# 16-FPGA-02a.net
KiCad netlist of a schematic drawn in Altium Designer
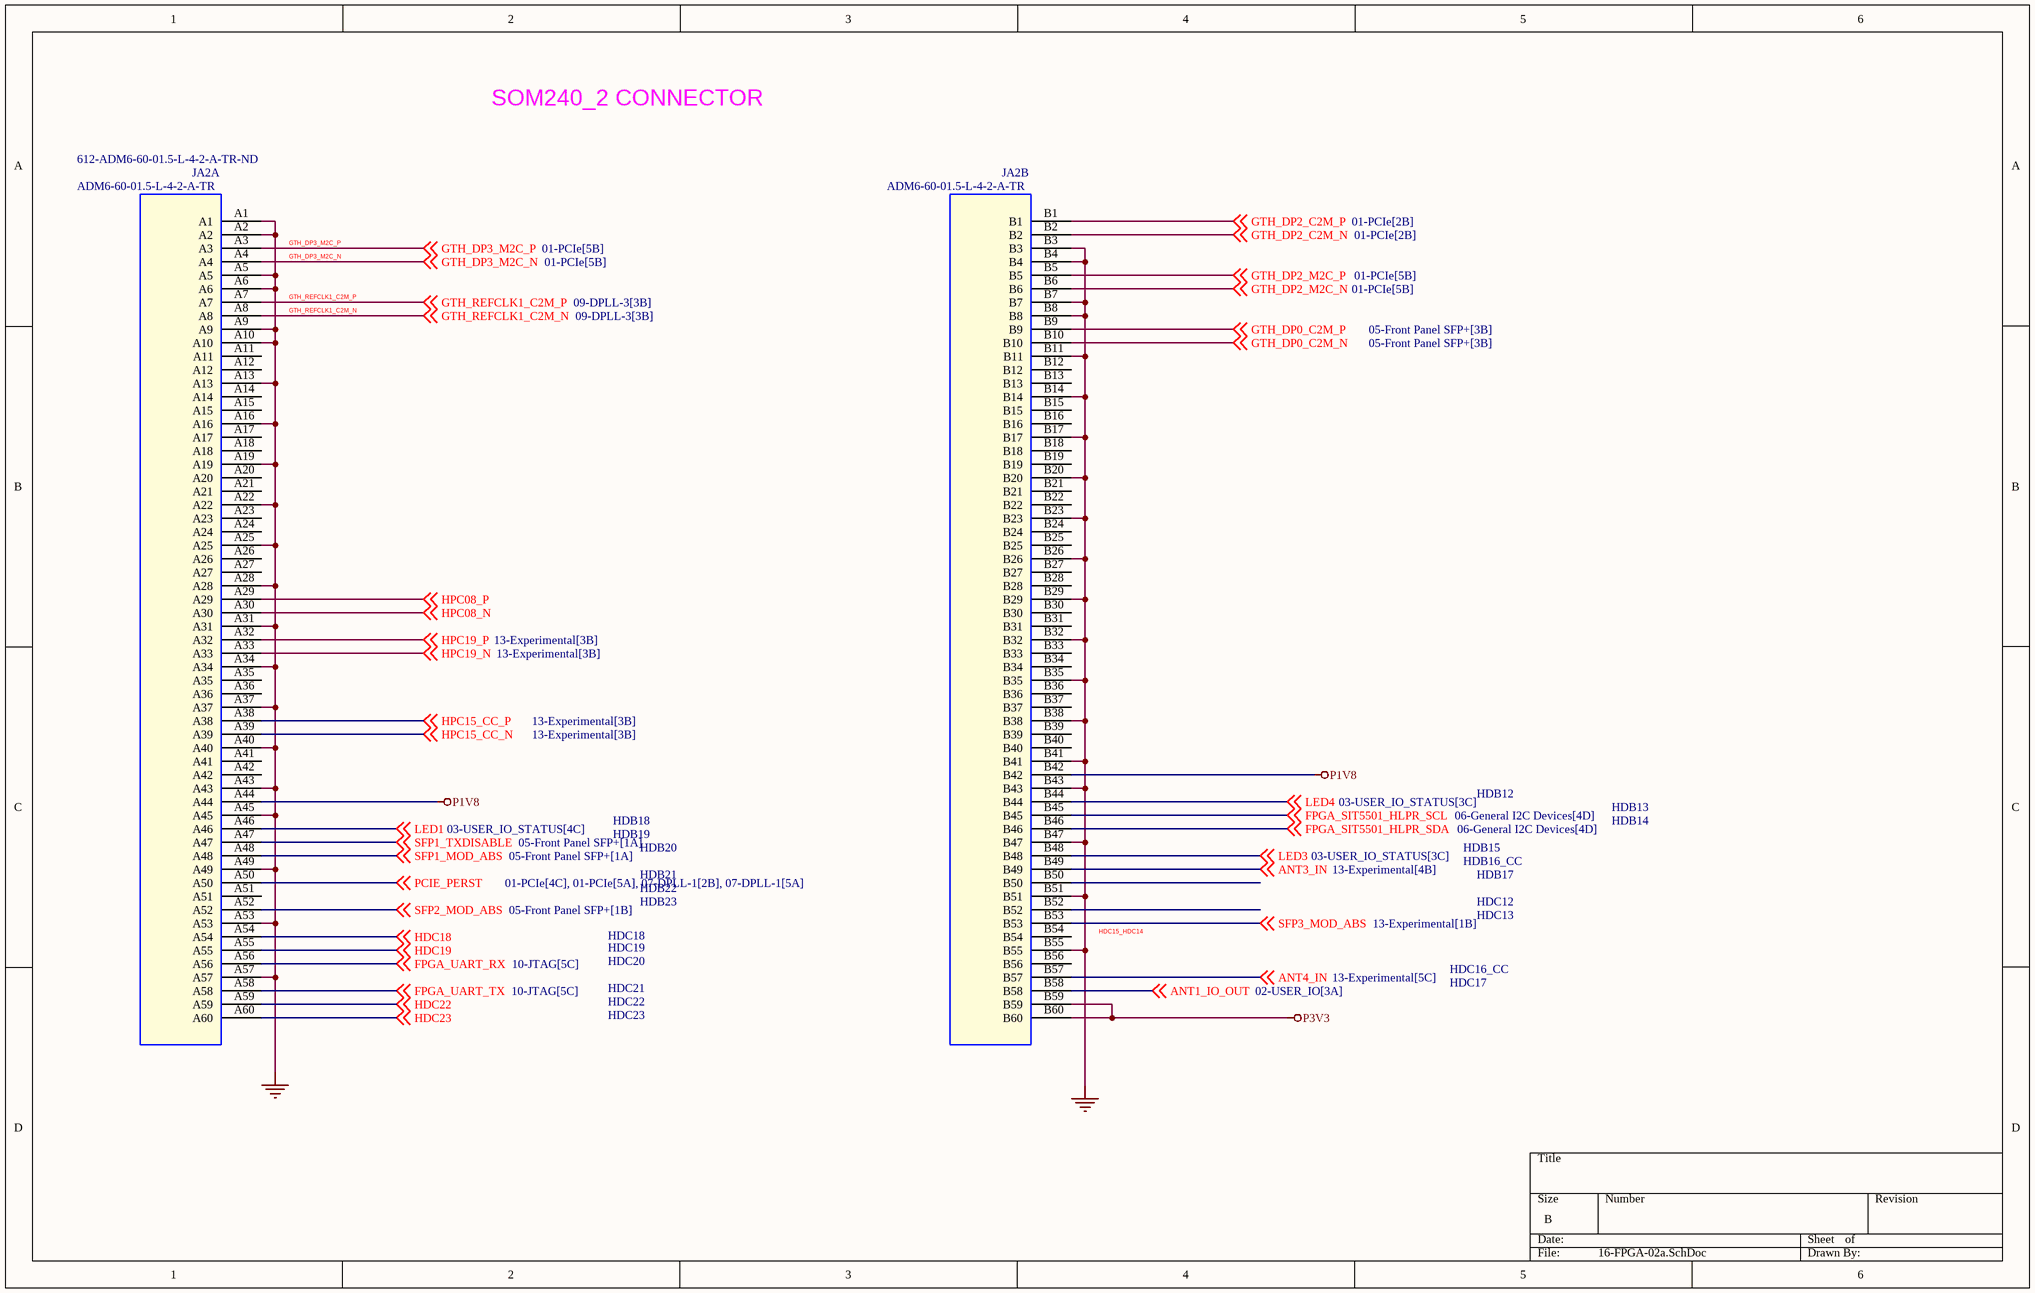
[diagram p0: 16-FPGA-02a.SchDoc]

(export (version "E")
  (design (tool "Eeschema 10.0.6"))
  (components
    (comp (ref "JA2")
      (value "ADM6-60-01.5-L-4-2-A-TR")
      (footprint "CON_SAMTEC_ADM6_60_4")
      (description "Conn Rcpt Male Vert 240 Pos 4x60 0.635mm P Black SMT")
      (fields
        (field (name "MANUFACTURER") "Samtec Inc.")
        (field (name "AGILE PART NUMBER") "CON-00383-01")
        (field (name "SUPPLIER PART NUMBER 1") "612-ADM6-60-01.5-L-4-2-A-TR-ND")
      )
      (libsource (lib "*") (part "SAMTEC-ADx6-60X4"))
    )
  )
  (nets
    (net (code "2") (name "ANT1_IO_OUT") (class "Default")
      (node (ref "JA2") (pin "B58") (pinfunction "B58_B58") (pintype "passive"))
    )
    (net (code "3") (name "ANT3_IN") (class "Default")
      (node (ref "JA2") (pin "B49") (pinfunction "B49_B49") (pintype "passive"))
    )
    (net (code "4") (name "ANT4_IN") (class "Default")
      (node (ref "JA2") (pin "B57") (pinfunction "B57_B57") (pintype "passive"))
    )
    (net (code "5") (name "FPGA_SIT5501_HLPR_SCL") (class "Default")
      (node (ref "JA2") (pin "B45") (pinfunction "B45_B45") (pintype "passive"))
    )
    (net (code "6") (name "FPGA_SIT5501_HLPR_SDA") (class "Default")
      (node (ref "JA2") (pin "B46") (pinfunction "B46_B46") (pintype "passive"))
    )
    (net (code "7") (name "FPGA_UART_RX") (class "Default")
      (node (ref "JA2") (pin "A56") (pinfunction "A56_A56") (pintype "passive"))
    )
    (net (code "8") (name "FPGA_UART_TX") (class "Default")
      (node (ref "JA2") (pin "A58") (pinfunction "A58_A58") (pintype "passive"))
    )
    (net (code "9") (name "GND") (class "Default")
      (node (ref "JA2") (pin "A1") (pinfunction "A1_A1") (pintype "passive"))
      (node (ref "JA2") (pin "A10") (pinfunction "A10_A10") (pintype "passive"))
      (node (ref "JA2") (pin "A13") (pinfunction "A13_A13") (pintype "passive"))
      (node (ref "JA2") (pin "A16") (pinfunction "A16_A16") (pintype "passive"))
      (node (ref "JA2") (pin "A19") (pinfunction "A19_A19") (pintype "passive"))
      (node (ref "JA2") (pin "A2") (pinfunction "A2_A2") (pintype "passive"))
      (node (ref "JA2") (pin "A22") (pinfunction "A22_A22") (pintype "passive"))
      (node (ref "JA2") (pin "A25") (pinfunction "A25_A25") (pintype "passive"))
      (node (ref "JA2") (pin "A28") (pinfunction "A28_A28") (pintype "passive"))
      (node (ref "JA2") (pin "A31") (pinfunction "A31_A31") (pintype "passive"))
      (node (ref "JA2") (pin "A34") (pinfunction "A34_A34") (pintype "passive"))
      (node (ref "JA2") (pin "A37") (pinfunction "A37_A37") (pintype "passive"))
      (node (ref "JA2") (pin "A40") (pinfunction "A40_A40") (pintype "passive"))
      (node (ref "JA2") (pin "A43") (pinfunction "A43_A43") (pintype "passive"))
      (node (ref "JA2") (pin "A45") (pinfunction "A45_A45") (pintype "passive"))
      (node (ref "JA2") (pin "A49") (pinfunction "A49_A49") (pintype "passive"))
      (node (ref "JA2") (pin "A5") (pinfunction "A5_A5") (pintype "passive"))
      (node (ref "JA2") (pin "A53") (pinfunction "A53_A53") (pintype "passive"))
      (node (ref "JA2") (pin "A57") (pinfunction "A57_A57") (pintype "passive"))
      (node (ref "JA2") (pin "A6") (pinfunction "A6_A6") (pintype "passive"))
      (node (ref "JA2") (pin "A9") (pinfunction "A9_A9") (pintype "passive"))
      (node (ref "JA2") (pin "B11") (pinfunction "B11_B11") (pintype "passive"))
      (node (ref "JA2") (pin "B14") (pinfunction "B14_B14") (pintype "passive"))
      (node (ref "JA2") (pin "B17") (pinfunction "B17_B17") (pintype "passive"))
      (node (ref "JA2") (pin "B20") (pinfunction "B20_B20") (pintype "passive"))
      (node (ref "JA2") (pin "B23") (pinfunction "B23_B23") (pintype "passive"))
      (node (ref "JA2") (pin "B26") (pinfunction "B26_B26") (pintype "passive"))
      (node (ref "JA2") (pin "B29") (pinfunction "B29_B29") (pintype "passive"))
      (node (ref "JA2") (pin "B3") (pinfunction "B3_B3") (pintype "passive"))
      (node (ref "JA2") (pin "B32") (pinfunction "B32_B32") (pintype "passive"))
      (node (ref "JA2") (pin "B35") (pinfunction "B35_B35") (pintype "passive"))
      (node (ref "JA2") (pin "B38") (pinfunction "B38_B38") (pintype "passive"))
      (node (ref "JA2") (pin "B4") (pinfunction "B4_B4") (pintype "passive"))
      (node (ref "JA2") (pin "B41") (pinfunction "B41_B41") (pintype "passive"))
      (node (ref "JA2") (pin "B43") (pinfunction "B43_B43") (pintype "passive"))
      (node (ref "JA2") (pin "B47") (pinfunction "B47_B47") (pintype "passive"))
      (node (ref "JA2") (pin "B51") (pinfunction "B51_B51") (pintype "passive"))
      (node (ref "JA2") (pin "B55") (pinfunction "B55_B55") (pintype "passive"))
      (node (ref "JA2") (pin "B7") (pinfunction "B7_B7") (pintype "passive"))
      (node (ref "JA2") (pin "B8") (pinfunction "B8_B8") (pintype "passive"))
    )
    (net (code "10") (name "GTH_DP0_C2M_N") (class "Default")
      (node (ref "JA2") (pin "B10") (pinfunction "B10_B10") (pintype "passive"))
    )
    (net (code "11") (name "GTH_DP0_C2M_P") (class "Default")
      (node (ref "JA2") (pin "B9") (pinfunction "B9_B9") (pintype "passive"))
    )
    (net (code "12") (name "GTH_DP2_C2M_N") (class "Default")
      (node (ref "JA2") (pin "B2") (pinfunction "B2_B2") (pintype "passive"))
    )
    (net (code "13") (name "GTH_DP2_C2M_P") (class "Default")
      (node (ref "JA2") (pin "B1") (pinfunction "B1_B1") (pintype "passive"))
    )
    (net (code "14") (name "GTH_DP2_M2C_N") (class "Default")
      (node (ref "JA2") (pin "B6") (pinfunction "B6_B6") (pintype "passive"))
    )
    (net (code "15") (name "GTH_DP2_M2C_P") (class "Default")
      (node (ref "JA2") (pin "B5") (pinfunction "B5_B5") (pintype "passive"))
    )
    (net (code "16") (name "GTH_DP3_M2C_N") (class "Default")
      (node (ref "JA2") (pin "A4") (pinfunction "A4_A4") (pintype "passive"))
    )
    (net (code "17") (name "GTH_DP3_M2C_P") (class "Default")
      (node (ref "JA2") (pin "A3") (pinfunction "A3_A3") (pintype "passive"))
    )
    (net (code "18") (name "GTH_REFCLK1_C2M_N") (class "Default")
      (node (ref "JA2") (pin "A8") (pinfunction "A8_A8") (pintype "passive"))
    )
    (net (code "19") (name "GTH_REFCLK1_C2M_P") (class "Default")
      (node (ref "JA2") (pin "A7") (pinfunction "A7_A7") (pintype "passive"))
    )
    (net (code "20") (name "HDC18") (class "Default")
      (node (ref "JA2") (pin "A54") (pinfunction "A54_A54") (pintype "passive"))
    )
    (net (code "21") (name "HDC19") (class "Default")
      (node (ref "JA2") (pin "A55") (pinfunction "A55_A55") (pintype "passive"))
    )
    (net (code "22") (name "HDC22") (class "Default")
      (node (ref "JA2") (pin "A59") (pinfunction "A59_A59") (pintype "passive"))
    )
    (net (code "23") (name "HDC23") (class "Default")
      (node (ref "JA2") (pin "A60") (pinfunction "A60_A60") (pintype "passive"))
    )
    (net (code "24") (name "HPC08_N") (class "Default")
      (node (ref "JA2") (pin "A30") (pinfunction "A30_A30") (pintype "passive"))
    )
    (net (code "25") (name "HPC08_P") (class "Default")
      (node (ref "JA2") (pin "A29") (pinfunction "A29_A29") (pintype "passive"))
    )
    (net (code "26") (name "HPC15_CC_N") (class "Default")
      (node (ref "JA2") (pin "A39") (pinfunction "A39_A39") (pintype "passive"))
    )
    (net (code "27") (name "HPC15_CC_P") (class "Default")
      (node (ref "JA2") (pin "A38") (pinfunction "A38_A38") (pintype "passive"))
    )
    (net (code "28") (name "HPC19_N") (class "Default")
      (node (ref "JA2") (pin "A33") (pinfunction "A33_A33") (pintype "passive"))
    )
    (net (code "29") (name "HPC19_P") (class "Default")
      (node (ref "JA2") (pin "A32") (pinfunction "A32_A32") (pintype "passive"))
    )
    (net (code "30") (name "LED1") (class "Default")
      (node (ref "JA2") (pin "A46") (pinfunction "A46_A46") (pintype "passive"))
    )
    (net (code "31") (name "LED3") (class "Default")
      (node (ref "JA2") (pin "B48") (pinfunction "B48_B48") (pintype "passive"))
    )
    (net (code "32") (name "LED4") (class "Default")
      (node (ref "JA2") (pin "B44") (pinfunction "B44_B44") (pintype "passive"))
    )
    (net (code "33") (name "P1V8") (class "Default")
      (node (ref "JA2") (pin "A44") (pinfunction "A44_A44") (pintype "passive"))
      (node (ref "JA2") (pin "B42") (pinfunction "B42_B42") (pintype "passive"))
    )
    (net (code "34") (name "P3V3") (class "Default")
      (node (ref "JA2") (pin "B59") (pinfunction "B59_B59") (pintype "passive"))
      (node (ref "JA2") (pin "B60") (pinfunction "B60_B60") (pintype "passive"))
    )
    (net (code "35") (name "PCIE_PERST") (class "Default")
      (node (ref "JA2") (pin "A50") (pinfunction "A50_A50") (pintype "passive"))
    )
    (net (code "36") (name "SFP1_MOD_ABS") (class "Default")
      (node (ref "JA2") (pin "A48") (pinfunction "A48_A48") (pintype "passive"))
    )
    (net (code "37") (name "SFP1_TXDISABLE") (class "Default")
      (node (ref "JA2") (pin "A47") (pinfunction "A47_A47") (pintype "passive"))
    )
    (net (code "38") (name "SFP2_MOD_ABS") (class "Default")
      (node (ref "JA2") (pin "A52") (pinfunction "A52_A52") (pintype "passive"))
    )
    (net (code "39") (name "SFP3_MOD_ABS") (class "Default")
      (node (ref "JA2") (pin "B53") (pinfunction "B53_B53") (pintype "passive"))
    )
    (net (code "40") (name "unconnected-(JA2-PadA11)") (class "Default")
      (node (ref "JA2") (pin "A11") (pinfunction "A11_A11") (pintype "passive"))
    )
    (net (code "41") (name "unconnected-(JA2-PadA12)") (class "Default")
      (node (ref "JA2") (pin "A12") (pinfunction "A12_A12") (pintype "passive"))
    )
    (net (code "42") (name "unconnected-(JA2-PadA14)") (class "Default")
      (node (ref "JA2") (pin "A14") (pinfunction "A14_A14") (pintype "passive"))
    )
    (net (code "43") (name "unconnected-(JA2-PadA15)") (class "Default")
      (node (ref "JA2") (pin "A15") (pinfunction "A15_A15") (pintype "passive"))
    )
    (net (code "44") (name "unconnected-(JA2-PadA17)") (class "Default")
      (node (ref "JA2") (pin "A17") (pinfunction "A17_A17") (pintype "passive"))
    )
    (net (code "45") (name "unconnected-(JA2-PadA18)") (class "Default")
      (node (ref "JA2") (pin "A18") (pinfunction "A18_A18") (pintype "passive"))
    )
    (net (code "46") (name "unconnected-(JA2-PadA20)") (class "Default")
      (node (ref "JA2") (pin "A20") (pinfunction "A20_A20") (pintype "passive"))
    )
    (net (code "47") (name "unconnected-(JA2-PadA21)") (class "Default")
      (node (ref "JA2") (pin "A21") (pinfunction "A21_A21") (pintype "passive"))
    )
    (net (code "48") (name "unconnected-(JA2-PadA23)") (class "Default")
      (node (ref "JA2") (pin "A23") (pinfunction "A23_A23") (pintype "passive"))
    )
    (net (code "49") (name "unconnected-(JA2-PadA24)") (class "Default")
      (node (ref "JA2") (pin "A24") (pinfunction "A24_A24") (pintype "passive"))
    )
    (net (code "50") (name "unconnected-(JA2-PadA26)") (class "Default")
      (node (ref "JA2") (pin "A26") (pinfunction "A26_A26") (pintype "passive"))
    )
    (net (code "51") (name "unconnected-(JA2-PadA27)") (class "Default")
      (node (ref "JA2") (pin "A27") (pinfunction "A27_A27") (pintype "passive"))
    )
    (net (code "52") (name "unconnected-(JA2-PadA35)") (class "Default")
      (node (ref "JA2") (pin "A35") (pinfunction "A35_A35") (pintype "passive"))
    )
    (net (code "53") (name "unconnected-(JA2-PadA36)") (class "Default")
      (node (ref "JA2") (pin "A36") (pinfunction "A36_A36") (pintype "passive"))
    )
    (net (code "54") (name "unconnected-(JA2-PadA41)") (class "Default")
      (node (ref "JA2") (pin "A41") (pinfunction "A41_A41") (pintype "passive"))
    )
    (net (code "55") (name "unconnected-(JA2-PadA42)") (class "Default")
      (node (ref "JA2") (pin "A42") (pinfunction "A42_A42") (pintype "passive"))
    )
    (net (code "56") (name "unconnected-(JA2-PadA51)") (class "Default")
      (node (ref "JA2") (pin "A51") (pinfunction "A51_A51") (pintype "passive"))
    )
    (net (code "57") (name "unconnected-(JA2-PadB12)") (class "Default")
      (node (ref "JA2") (pin "B12") (pinfunction "B12_B12") (pintype "passive"))
    )
    (net (code "58") (name "unconnected-(JA2-PadB13)") (class "Default")
      (node (ref "JA2") (pin "B13") (pinfunction "B13_B13") (pintype "passive"))
    )
    (net (code "59") (name "unconnected-(JA2-PadB15)") (class "Default")
      (node (ref "JA2") (pin "B15") (pinfunction "B15_B15") (pintype "passive"))
    )
    (net (code "60") (name "unconnected-(JA2-PadB16)") (class "Default")
      (node (ref "JA2") (pin "B16") (pinfunction "B16_B16") (pintype "passive"))
    )
    (net (code "61") (name "unconnected-(JA2-PadB18)") (class "Default")
      (node (ref "JA2") (pin "B18") (pinfunction "B18_B18") (pintype "passive"))
    )
    (net (code "62") (name "unconnected-(JA2-PadB19)") (class "Default")
      (node (ref "JA2") (pin "B19") (pinfunction "B19_B19") (pintype "passive"))
    )
    (net (code "63") (name "unconnected-(JA2-PadB21)") (class "Default")
      (node (ref "JA2") (pin "B21") (pinfunction "B21_B21") (pintype "passive"))
    )
    (net (code "64") (name "unconnected-(JA2-PadB22)") (class "Default")
      (node (ref "JA2") (pin "B22") (pinfunction "B22_B22") (pintype "passive"))
    )
    (net (code "65") (name "unconnected-(JA2-PadB24)") (class "Default")
      (node (ref "JA2") (pin "B24") (pinfunction "B24_B24") (pintype "passive"))
    )
    (net (code "66") (name "unconnected-(JA2-PadB25)") (class "Default")
      (node (ref "JA2") (pin "B25") (pinfunction "B25_B25") (pintype "passive"))
    )
    (net (code "67") (name "unconnected-(JA2-PadB27)") (class "Default")
      (node (ref "JA2") (pin "B27") (pinfunction "B27_B27") (pintype "passive"))
    )
    (net (code "68") (name "unconnected-(JA2-PadB28)") (class "Default")
      (node (ref "JA2") (pin "B28") (pinfunction "B28_B28") (pintype "passive"))
    )
    (net (code "69") (name "unconnected-(JA2-PadB30)") (class "Default")
      (node (ref "JA2") (pin "B30") (pinfunction "B30_B30") (pintype "passive"))
    )
    (net (code "70") (name "unconnected-(JA2-PadB31)") (class "Default")
      (node (ref "JA2") (pin "B31") (pinfunction "B31_B31") (pintype "passive"))
    )
    (net (code "71") (name "unconnected-(JA2-PadB33)") (class "Default")
      (node (ref "JA2") (pin "B33") (pinfunction "B33_B33") (pintype "passive"))
    )
    (net (code "72") (name "unconnected-(JA2-PadB34)") (class "Default")
      (node (ref "JA2") (pin "B34") (pinfunction "B34_B34") (pintype "passive"))
    )
    (net (code "73") (name "unconnected-(JA2-PadB36)") (class "Default")
      (node (ref "JA2") (pin "B36") (pinfunction "B36_B36") (pintype "passive"))
    )
    (net (code "74") (name "unconnected-(JA2-PadB37)") (class "Default")
      (node (ref "JA2") (pin "B37") (pinfunction "B37_B37") (pintype "passive"))
    )
    (net (code "75") (name "unconnected-(JA2-PadB39)") (class "Default")
      (node (ref "JA2") (pin "B39") (pinfunction "B39_B39") (pintype "passive"))
    )
    (net (code "76") (name "unconnected-(JA2-PadB40)") (class "Default")
      (node (ref "JA2") (pin "B40") (pinfunction "B40_B40") (pintype "passive"))
    )
    (net (code "77") (name "unconnected-(JA2-PadB50)") (class "Default")
      (node (ref "JA2") (pin "B50") (pinfunction "B50_B50") (pintype "passive"))
    )
    (net (code "78") (name "unconnected-(JA2-PadB52)") (class "Default")
      (node (ref "JA2") (pin "B52") (pinfunction "B52_B52") (pintype "passive"))
    )
    (net (code "79") (name "unconnected-(JA2-PadB54)") (class "Default")
      (node (ref "JA2") (pin "B54") (pinfunction "B54_B54") (pintype "passive"))
    )
    (net (code "80") (name "unconnected-(JA2-PadB56)") (class "Default")
      (node (ref "JA2") (pin "B56") (pinfunction "B56_B56") (pintype "passive"))
    )
  )
)
